# mas-cdc.net
KiCad netlist of a schematic drawn in Altium Designer
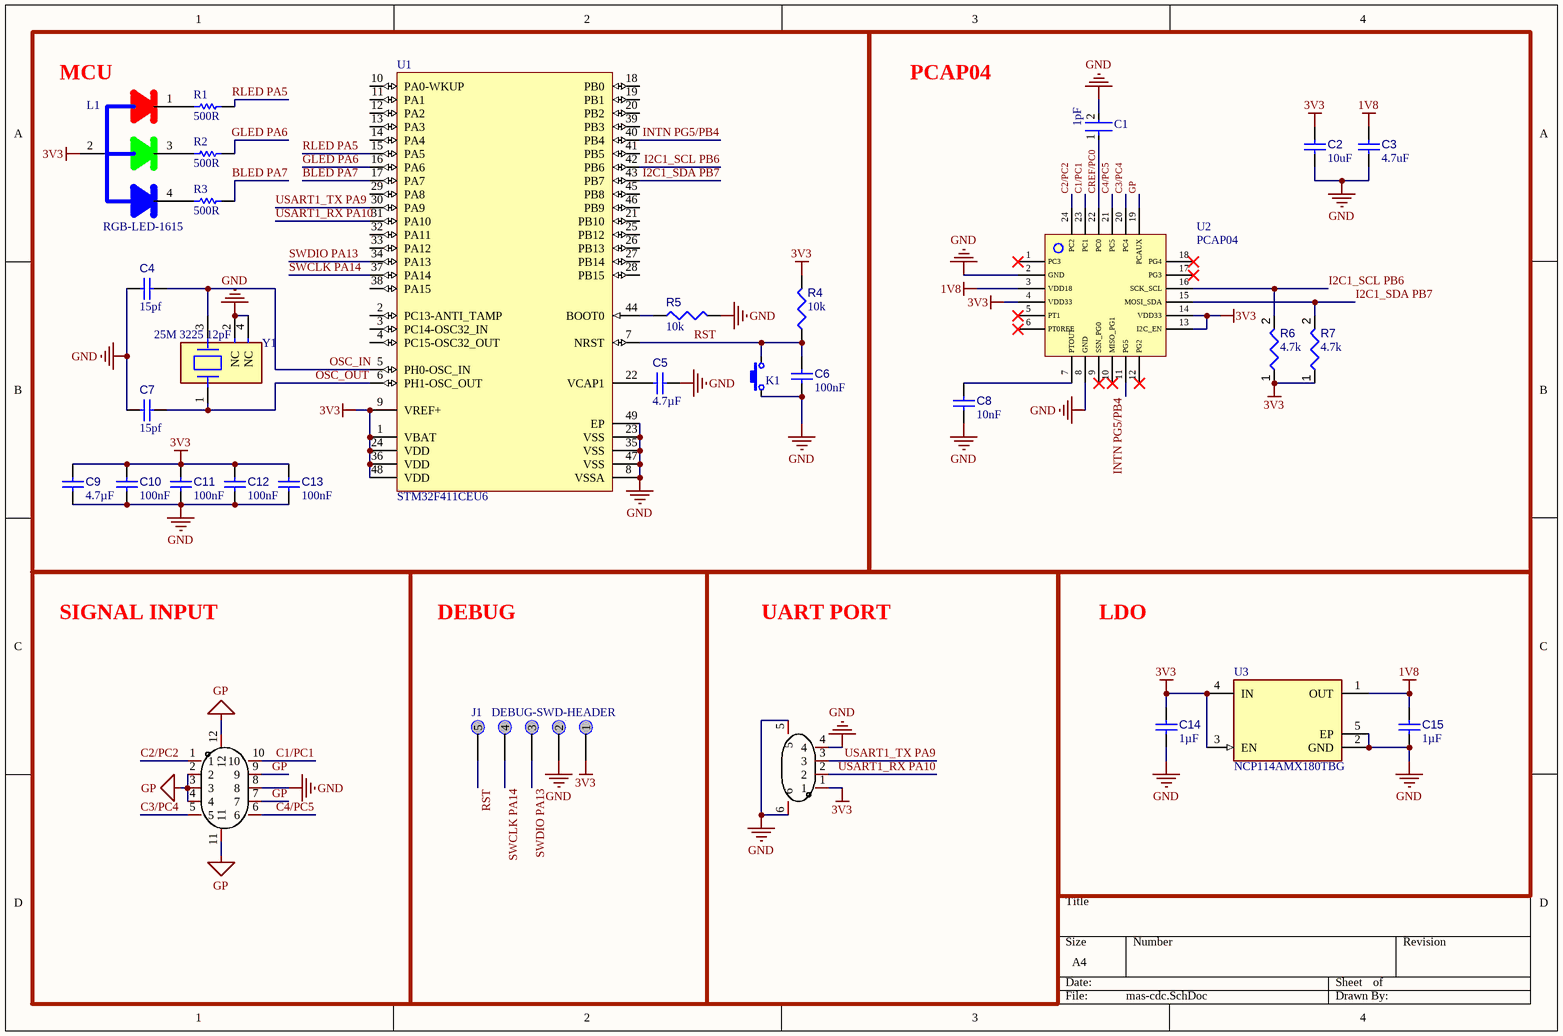
[diagram p0: mas-cdc.SchDoc]

(export (version "E")
  (design (tool "Eeschema 10.0.6"))
  (components
    (comp (ref "C1")
      (value "1pF")
      (footprint "FP-GRM033-0_03-IPC_B")
      (description "Chip Multilayer Ceramic Capacitors for General Purpose, 0201, 1.0pF, C0G, 30ppm/°C, 0.05pF, 50V")
      (libsource (lib "Altium Content Vault") (part "b4654b650e69147ec39a6b967a45e02"))
    )
    (comp (ref "C2")
      (value "10uF")
      (footprint "CAPC0402(1005)60_L")
      (description "Chip Capacitor, 10µF +/-40%, 6.3V, 0402, Thickness 0.6 mm")
      (fields (field (name "TOLERANCE") "10%") (field (name "Comment") "Capacitor 10µF +/-40% 6.3V 0402"))
      (libsource (lib "DigiPCBA Workspace") (part "CAP-NP-2"))
    )
    (comp (ref "C3")
      (value "4.7uF")
      (footprint "CAPC0402(1005)60_L")
      (description "Chip Capacitor, 10µF +/-40%, 6.3V, 0402, Thickness 0.6 mm")
      (fields (field (name "TOLERANCE") "10%") (field (name "Comment") "Capacitor 10µF +/-40% 6.3V 0402"))
      (libsource (lib "DigiPCBA Workspace") (part "CAP-NP-2"))
    )
    (comp (ref "C4")
      (value "15pf")
      (footprint "CAPC0402(1005)60_L")
      (description "Chip Capacitor, 100nF +/-20%, 25V, 0402, Thickness 0.6 mm")
      (fields (field (name "TOLERANCE") "10%") (field (name "Comment") "Capacitor 100nF +/-20% 25V 0402"))
      (libsource (lib "DigiPCBA Workspace") (part "CAP-NP-2"))
    )
    (comp (ref "C5")
      (value "4.7µF")
      (footprint "CAPC0603(1608)100_L")
      (description "Chip Capacitor, 4.7µF +/-20%, 10V, 0603, Thickness 1 mm")
      (fields (field (name "TOLERANCE") "10%") (field (name "Comment") "Capacitor 4.7µF +/-20% 10V 0603"))
      (libsource (lib "DigiPCBA Workspace") (part "CAP-NP-2"))
    )
    (comp (ref "C6")
      (value "100nF")
      (footprint "CAPC0402(1005)60_L")
      (description "Chip Capacitor, 100nF +/-20%, 25V, 0402, Thickness 0.6 mm")
      (fields (field (name "TOLERANCE") "10%") (field (name "Comment") "Capacitor 100nF +/-20% 25V 0402"))
      (libsource (lib "DigiPCBA Workspace") (part "CAP-NP-2"))
    )
    (comp (ref "C7")
      (value "15pf")
      (footprint "CAPC0402(1005)60_L")
      (description "Chip Capacitor, 100nF +/-20%, 25V, 0402, Thickness 0.6 mm")
      (fields (field (name "TOLERANCE") "10%") (field (name "Comment") "Capacitor 100nF +/-20% 25V 0402"))
      (libsource (lib "DigiPCBA Workspace") (part "CAP-NP-2"))
    )
    (comp (ref "C8")
      (value "10nF")
      (footprint "CAPC0402(1005)60_L")
      (description "Chip Capacitor, 10nF +/-20%, 50V, 0402, Thickness 0.6 mm")
      (fields (field (name "TOLERANCE") "5%") (field (name "Comment") "Capacitor 10nF +/-20% 50V 0402"))
      (libsource (lib "DigiPCBA Workspace") (part "CAP-NP-2"))
    )
    (comp (ref "C9")
      (value "4.7µF")
      (footprint "CAPC0603(1608)100_L")
      (description "Chip Capacitor, 4.7µF +/-20%, 10V, 0603, Thickness 1 mm")
      (fields (field (name "TOLERANCE") "10%") (field (name "Comment") "Capacitor 4.7µF +/-20% 10V 0603"))
      (libsource (lib "DigiPCBA Workspace") (part "CAP-NP-2"))
    )
    (comp (ref "C10")
      (value "100nF")
      (footprint "CAPC0402(1005)60_L")
      (description "Chip Capacitor, 100nF +/-20%, 25V, 0402, Thickness 0.6 mm")
      (fields (field (name "TOLERANCE") "10%") (field (name "Comment") "Capacitor 100nF +/-20% 25V 0402"))
      (libsource (lib "DigiPCBA Workspace") (part "CAP-NP-2"))
    )
    (comp (ref "C11")
      (value "100nF")
      (footprint "CAPC0402(1005)60_L")
      (description "Chip Capacitor, 100nF +/-20%, 25V, 0402, Thickness 0.6 mm")
      (fields (field (name "TOLERANCE") "10%") (field (name "Comment") "Capacitor 100nF +/-20% 25V 0402"))
      (libsource (lib "DigiPCBA Workspace") (part "CAP-NP-2"))
    )
    (comp (ref "C12")
      (value "100nF")
      (footprint "CAPC0402(1005)60_L")
      (description "Chip Capacitor, 100nF +/-20%, 25V, 0402, Thickness 0.6 mm")
      (fields (field (name "TOLERANCE") "10%") (field (name "Comment") "Capacitor 100nF +/-20% 25V 0402"))
      (libsource (lib "DigiPCBA Workspace") (part "CAP-NP-2"))
    )
    (comp (ref "C13")
      (value "100nF")
      (footprint "CAPC0402(1005)60_L")
      (description "Chip Capacitor, 100nF +/-20%, 25V, 0402, Thickness 0.6 mm")
      (fields (field (name "TOLERANCE") "10%") (field (name "Comment") "Capacitor 100nF +/-20% 25V 0402"))
      (libsource (lib "DigiPCBA Workspace") (part "CAP-NP-2"))
    )
    (comp (ref "C14")
      (value "1µF")
      (footprint "CAPC0402(1005)60_L")
      (description "Chip Capacitor, 1µF +/-20%, 10V, 0402, Thickness 0.6 mm")
      (fields (field (name "TOLERANCE") "10%") (field (name "Comment") "Capacitor 1µF +/-20% 10V 0402"))
      (libsource (lib "DigiPCBA Workspace") (part "CAP-NP-2"))
    )
    (comp (ref "C15")
      (value "1µF")
      (footprint "CAPC0402(1005)60_L")
      (description "Chip Capacitor, 1µF +/-20%, 10V, 0402, Thickness 0.6 mm")
      (fields (field (name "TOLERANCE") "10%") (field (name "Comment") "Capacitor 1µF +/-20% 10V 0402"))
      (libsource (lib "DigiPCBA Workspace") (part "CAP-NP-2"))
    )
    (comp (ref "CN1")
      (value "SH1.0-4P")
      (footprint "CONN-SMD_4P-P1.00_WF10004-01200")
      (description "连接器")
      (fields (field (name "MANUFACTURER") "ATOM(爱特姆)") (field (name "MANUFACTURER PART") "WF10004-01200"))
      (libsource (lib "LGSchlib") (part "SH1.0-4P"))
    )
    (comp (ref "J1")
      (value "DEBUG-SWD-HEADER")
      (footprint "DEBUG-SWD-HEADER-Footprint-1")
      (description "1.27MM 5P 测试/调试/下载焊点")
      (libsource (lib "DigiPCBA Workspace") (part "DEBUG-SWD-HEADER-Symbol-1"))
    )
    (comp (ref "J2")
      (value "BM24-10DS/2-0.35V(51)")
      (footprint "CONN-SMD_BM24-10DS-2-0.35V-51")
      (description "板对板连接器")
      (fields (field (name "MANUFACTURER") "HRS(广濑)"))
      (libsource (lib "LG_Integrated_Library") (part "BM24-10DS/2-0.35V(51)"))
    )
    (comp (ref "K1")
      (value "Button")
      (footprint "SW-SMD_ST-1185X")
      (libsource (lib "LG_Integrated_Library") (part "Button"))
    )
    (comp (ref "L1")
      (value "RGB-LED-1615")
      (footprint "RGB-LED-1615-Footprint-1")
      (description "RGB LED")
      (libsource (lib "DigiPCBA Workspace") (part "RGB-LED-1615-Symbol-1"))
    )
    (comp (ref "R1")
      (value "500R")
      (footprint "RESC0603X26X15ML03T05")
      (fields (field (name "PART NUMBER") "RK73H1HTTC1002F") (field (name "MANUFACTURER") "KOA Speer"))
      (libsource (lib "Altium Content Vault") (part "RES"))
    )
    (comp (ref "R2")
      (value "500R")
      (footprint "RESC0603X26X15ML03T05")
      (fields (field (name "PART NUMBER") "RK73H1HTTC1002F") (field (name "MANUFACTURER") "KOA Speer"))
      (libsource (lib "Altium Content Vault") (part "RES"))
    )
    (comp (ref "R3")
      (value "500R")
      (footprint "RESC0603X26X15ML03T05")
      (fields (field (name "PART NUMBER") "RK73H1HTTC1002F") (field (name "MANUFACTURER") "KOA Speer"))
      (libsource (lib "Altium Content Vault") (part "RES"))
    )
    (comp (ref "R4")
      (value "10k")
      (footprint "RESC0402(1005)_L")
      (description "Chip Resistor, 10 kOhms, +/-1 %, 63 mW, -55 to 125 degC, 0402")
      (fields (field (name "POWER") "63mW") (field (name "TOLERANCE") "1%"))
      (libsource (lib "") (part "RES-2_1"))
    )
    (comp (ref "R5")
      (value "10k")
      (footprint "RESC0402(1005)_L")
      (description "Chip Resistor, 10 kOhms, +/-1 %, 63 mW, -55 to 125 degC, 0402")
      (fields (field (name "POWER") "63mW") (field (name "TOLERANCE") "1%"))
      (libsource (lib "") (part "RES-2_1"))
    )
    (comp (ref "R6")
      (value "4.7k")
      (footprint "RESC0402(1005)_L")
      (description "Chip Resistor, 4,7 kOhms, +/-1 %, 63 mW, -55 to 155 degC, 0402")
      (fields (field (name "POWER") "63mW") (field (name "TOLERANCE") "1%"))
      (libsource (lib "DigiPCBA Workspace") (part "RES-2"))
    )
    (comp (ref "R7")
      (value "4.7k")
      (footprint "RESC0402(1005)_L")
      (description "Chip Resistor, 4,7 kOhms, +/-1 %, 63 mW, -55 to 155 degC, 0402")
      (fields (field (name "POWER") "63mW") (field (name "TOLERANCE") "1%"))
      (libsource (lib "DigiPCBA Workspace") (part "RES-2"))
    )
    (comp (ref "U1")
      (value "STM32F411CEU6")
      (footprint "STM-UFQFPN48_L")
      (libsource (lib "LG_Integrated_Library") (part "STM32F411CEU6-2"))
    )
    (comp (ref "U2")
      (value "PCAP04")
      (footprint "QFN-24-PAD")
      (description "CDC IC")
      (libsource (lib "LG_Integrated_Library") (part "PCAP04"))
    )
    (comp (ref "U3")
      (value "NCP114AMX180TBG")
      (footprint "FP-517CU-MFG")
      (description "IC REG LINEAR 1.8V 300MA 4UDFN")
      (fields
        (field (name "MANUFACTURER") "ON Semiconductor")
        (field (name "OCTOPART") "https://octopart.com/ncp114amx180tbg-on+semiconductor-56808172")
      )
      (libsource (lib "Altium Content Vault") (part "d482fde4c46c8d3b68fd86b21119a5c"))
    )
    (comp (ref "Y1")
      (value "25M 3225 12pF")
      (footprint "FP-CX3225GB-MFG")
      (description "CRYSTAL 16.0000MHZ 8PF SMD")
      (fields (field (name "TOLERANCE") "20ppm"))
      (libsource (lib "Altium Content Vault") (part "485821f88a3d0e4767168cc8d80ed41"))
    )
  )
  (nets
    (net (code "1") (name "/BLED PA7") (class "Default")
      (node (ref "R3") (pin "2") (pinfunction "2_2") (pintype "passive"))
      (node (ref "U1") (pin "17") (pinfunction "PA7_17") (pintype "bidirectional"))
    )
    (net (code "2") (name "/C1{slash}PC1") (class "Default")
      (node (ref "J2") (pin "10") (pinfunction "10_10") (pintype "passive"))
      (node (ref "U2") (pin "23") (pinfunction "PC1_23") (pintype "passive"))
    )
    (net (code "3") (name "/C2{slash}PC2") (class "Default")
      (node (ref "J2") (pin "1") (pinfunction "1_1") (pintype "passive"))
      (node (ref "U2") (pin "24") (pinfunction "PC2_24") (pintype "passive"))
    )
    (net (code "4") (name "/C3{slash}PC4") (class "Default")
      (node (ref "J2") (pin "5") (pinfunction "5_5") (pintype "passive"))
      (node (ref "U2") (pin "20") (pinfunction "PC4_20") (pintype "passive"))
    )
    (net (code "5") (name "/C4{slash}PC5") (class "Default")
      (node (ref "J2") (pin "6") (pinfunction "6_6") (pintype "passive"))
      (node (ref "U2") (pin "21") (pinfunction "PC5_21") (pintype "passive"))
    )
    (net (code "6") (name "/CREF{slash}PC0") (class "Default")
      (node (ref "C1") (pin "1") (pinfunction "1_1") (pintype "passive"))
      (node (ref "U2") (pin "22") (pinfunction "PC0_22") (pintype "passive"))
    )
    (net (code "7") (name "/GLED PA6") (class "Default")
      (node (ref "R2") (pin "2") (pinfunction "2_2") (pintype "passive"))
      (node (ref "U1") (pin "16") (pinfunction "PA6_16") (pintype "bidirectional"))
    )
    (net (code "8") (name "/I2C1_SCL PB6") (class "Default")
      (node (ref "R6") (pin "2") (pinfunction "2_2") (pintype "passive"))
      (node (ref "U1") (pin "42") (pinfunction "PB6_42") (pintype "bidirectional"))
      (node (ref "U2") (pin "16") (pinfunction "SCK_SCL_16") (pintype "passive"))
    )
    (net (code "9") (name "/I2C1_SDA PB7") (class "Default")
      (node (ref "R7") (pin "2") (pinfunction "2_2") (pintype "passive"))
      (node (ref "U1") (pin "43") (pinfunction "PB7_43") (pintype "bidirectional"))
      (node (ref "U2") (pin "15") (pinfunction "MOSI_SDA_15") (pintype "passive"))
    )
    (net (code "10") (name "/INTN PG5{slash}PB4") (class "Default")
      (node (ref "U1") (pin "40") (pinfunction "PB4_40") (pintype "bidirectional"))
      (node (ref "U2") (pin "11") (pinfunction "PG5_11") (pintype "passive"))
    )
    (net (code "11") (name "/OSC_IN") (class "Default")
      (node (ref "C4") (pin "1") (pinfunction "1_1") (pintype "passive"))
      (node (ref "U1") (pin "5") (pinfunction "PH0-OSC_IN_5") (pintype "bidirectional"))
      (node (ref "Y1") (pin "3") (pinfunction "2_HOT_3") (pintype "passive"))
    )
    (net (code "12") (name "/OSC_OUT") (class "Default")
      (node (ref "C7") (pin "1") (pinfunction "1_1") (pintype "passive"))
      (node (ref "U1") (pin "6") (pinfunction "PH1-OSC_OUT_6") (pintype "bidirectional"))
      (node (ref "Y1") (pin "1") (pinfunction "1_HOT_1") (pintype "passive"))
    )
    (net (code "13") (name "/RLED PA5") (class "Default")
      (node (ref "R1") (pin "2") (pinfunction "2_2") (pintype "passive"))
      (node (ref "U1") (pin "15") (pinfunction "PA5_15") (pintype "bidirectional"))
    )
    (net (code "14") (name "/RST") (class "Default")
      (node (ref "C6") (pin "2") (pinfunction "2_2") (pintype "passive"))
      (node (ref "J1") (pin "5") (pinfunction "5_5") (pintype "passive"))
      (node (ref "K1") (pin "2") (pinfunction "2_2") (pintype "passive"))
      (node (ref "R4") (pin "1") (pinfunction "1_1") (pintype "passive"))
      (node (ref "U1") (pin "7") (pinfunction "NRST_7") (pintype "bidirectional"))
    )
    (net (code "15") (name "/SWCLK PA14") (class "Default")
      (node (ref "J1") (pin "4") (pinfunction "4_4") (pintype "passive"))
      (node (ref "U1") (pin "37") (pinfunction "PA14_37") (pintype "bidirectional"))
    )
    (net (code "16") (name "/SWDIO PA13") (class "Default")
      (node (ref "J1") (pin "3") (pinfunction "3_3") (pintype "passive"))
      (node (ref "U1") (pin "34") (pinfunction "PA13_34") (pintype "bidirectional"))
    )
    (net (code "17") (name "/USART1_RX PA10") (class "Default")
      (node (ref "CN1") (pin "2") (pinfunction "2_2") (pintype "passive"))
      (node (ref "U1") (pin "31") (pinfunction "PA10_31") (pintype "bidirectional"))
    )
    (net (code "18") (name "/USART1_TX PA9") (class "Default")
      (node (ref "CN1") (pin "3") (pinfunction "3_3") (pintype "passive"))
      (node (ref "U1") (pin "30") (pinfunction "PA9_30") (pintype "bidirectional"))
    )
    (net (code "19") (name "1V8") (class "Default")
      (node (ref "C15") (pin "1") (pinfunction "1_1") (pintype "passive"))
      (node (ref "C3") (pin "2") (pinfunction "2_2") (pintype "passive"))
      (node (ref "U2") (pin "3") (pinfunction "VDD18_3") (pintype "passive"))
      (node (ref "U3") (pin "1") (pinfunction "OUT_1") (pintype "power_in"))
    )
    (net (code "20") (name "3V3") (class "Default")
      (node (ref "C10") (pin "2") (pinfunction "2_2") (pintype "passive"))
      (node (ref "C11") (pin "2") (pinfunction "2_2") (pintype "passive"))
      (node (ref "C12") (pin "2") (pinfunction "2_2") (pintype "passive"))
      (node (ref "C13") (pin "2") (pinfunction "2_2") (pintype "passive"))
      (node (ref "C14") (pin "1") (pinfunction "1_1") (pintype "passive"))
      (node (ref "C2") (pin "2") (pinfunction "2_2") (pintype "passive"))
      (node (ref "C9") (pin "2") (pinfunction "2_2") (pintype "passive"))
      (node (ref "CN1") (pin "1") (pinfunction "1_1") (pintype "passive"))
      (node (ref "J1") (pin "1") (pinfunction "1_1") (pintype "passive"))
      (node (ref "L1") (pin "2") (pinfunction "COM+_2") (pintype "passive"))
      (node (ref "R4") (pin "2") (pinfunction "2_2") (pintype "passive"))
      (node (ref "R6") (pin "1") (pinfunction "1_1") (pintype "passive"))
      (node (ref "R7") (pin "1") (pinfunction "1_1") (pintype "passive"))
      (node (ref "U1") (pin "1") (pinfunction "VBAT_1") (pintype "power_in"))
      (node (ref "U1") (pin "24") (pinfunction "VDD_24") (pintype "power_in"))
      (node (ref "U1") (pin "36") (pinfunction "VDD_36") (pintype "power_in"))
      (node (ref "U1") (pin "48") (pinfunction "VDD_48") (pintype "power_in"))
      (node (ref "U1") (pin "9") (pinfunction "VREF+_9") (pintype "power_in"))
      (node (ref "U2") (pin "13") (pinfunction "I2C_EN_13") (pintype "passive"))
      (node (ref "U2") (pin "14") (pinfunction "VDD33_14") (pintype "passive"))
      (node (ref "U2") (pin "4") (pinfunction "VDD33_4") (pintype "passive"))
      (node (ref "U3") (pin "3") (pinfunction "EN_3") (pintype "input"))
      (node (ref "U3") (pin "4") (pinfunction "IN_4") (pintype "power_in"))
    )
    (net (code "21") (name "GND") (class "Default")
      (node (ref "C1") (pin "2") (pinfunction "2_2") (pintype "passive"))
      (node (ref "C10") (pin "1") (pinfunction "1_1") (pintype "passive"))
      (node (ref "C11") (pin "1") (pinfunction "1_1") (pintype "passive"))
      (node (ref "C12") (pin "1") (pinfunction "1_1") (pintype "passive"))
      (node (ref "C13") (pin "1") (pinfunction "1_1") (pintype "passive"))
      (node (ref "C14") (pin "2") (pinfunction "2_2") (pintype "passive"))
      (node (ref "C15") (pin "2") (pinfunction "2_2") (pintype "passive"))
      (node (ref "C2") (pin "1") (pinfunction "1_1") (pintype "passive"))
      (node (ref "C3") (pin "1") (pinfunction "1_1") (pintype "passive"))
      (node (ref "C4") (pin "2") (pinfunction "2_2") (pintype "passive"))
      (node (ref "C5") (pin "2") (pinfunction "2_2") (pintype "passive"))
      (node (ref "C6") (pin "1") (pinfunction "1_1") (pintype "passive"))
      (node (ref "C7") (pin "2") (pinfunction "2_2") (pintype "passive"))
      (node (ref "C8") (pin "1") (pinfunction "1_1") (pintype "passive"))
      (node (ref "C9") (pin "1") (pinfunction "1_1") (pintype "passive"))
      (node (ref "CN1") (pin "4") (pinfunction "4_4") (pintype "passive"))
      (node (ref "CN1") (pin "5") (pinfunction "5_5") (pintype "passive"))
      (node (ref "CN1") (pin "6") (pinfunction "6_6") (pintype "passive"))
      (node (ref "J1") (pin "2") (pinfunction "2_2") (pintype "passive"))
      (node (ref "J2") (pin "8") (pinfunction "8_8") (pintype "passive"))
      (node (ref "K1") (pin "1") (pinfunction "1_1") (pintype "passive"))
      (node (ref "R5") (pin "2") (pinfunction "2_2") (pintype "passive"))
      (node (ref "U1") (pin "23") (pinfunction "VSS_23") (pintype "power_in"))
      (node (ref "U1") (pin "35") (pinfunction "VSS_35") (pintype "power_in"))
      (node (ref "U1") (pin "47") (pinfunction "VSS_47") (pintype "power_in"))
      (node (ref "U1") (pin "49") (pinfunction "EP_49") (pintype "power_in"))
      (node (ref "U1") (pin "8") (pinfunction "VSSA_8") (pintype "power_in"))
      (node (ref "U2") (pin "2") (pinfunction "GND_2") (pintype "passive"))
      (node (ref "U2") (pin "8") (pinfunction "GND_8") (pintype "passive"))
      (node (ref "U3") (pin "2") (pinfunction "GND_2") (pintype "power_in"))
      (node (ref "U3") (pin "5") (pinfunction "EP_5") (pintype "power_in"))
      (node (ref "Y1") (pin "2") (pinfunction "NC_2") (pintype "passive"))
      (node (ref "Y1") (pin "4") (pinfunction "NC_4") (pintype "passive"))
    )
    (net (code "22") (name "GP") (class "Default")
      (node (ref "J2") (pin "11") (pinfunction "11_11") (pintype "passive"))
      (node (ref "J2") (pin "12") (pinfunction "12_12") (pintype "passive"))
      (node (ref "J2") (pin "2") (pinfunction "2_2") (pintype "passive"))
      (node (ref "J2") (pin "3") (pinfunction "3_3") (pintype "passive"))
      (node (ref "J2") (pin "4") (pinfunction "4_4") (pintype "passive"))
      (node (ref "J2") (pin "7") (pinfunction "7_7") (pintype "passive"))
      (node (ref "J2") (pin "9") (pinfunction "9_9") (pintype "passive"))
      (node (ref "U2") (pin "19") (pinfunction "PCAUX_19") (pintype "passive"))
    )
    (net (code "23") (name "Net-(L1-B)") (class "Default")
      (node (ref "L1") (pin "4") (pinfunction "B_4") (pintype "passive"))
      (node (ref "R3") (pin "1") (pinfunction "1_1") (pintype "passive"))
    )
    (net (code "24") (name "Net-(L1-G)") (class "Default")
      (node (ref "L1") (pin "3") (pinfunction "G_3") (pintype "passive"))
      (node (ref "R2") (pin "1") (pinfunction "1_1") (pintype "passive"))
    )
    (net (code "25") (name "Net-(L1-R)") (class "Default")
      (node (ref "L1") (pin "1") (pinfunction "R_1") (pintype "passive"))
      (node (ref "R1") (pin "1") (pinfunction "1_1") (pintype "passive"))
    )
    (net (code "26") (name "Net-(U1-BOOT0)") (class "Default")
      (node (ref "R5") (pin "1") (pinfunction "1_1") (pintype "passive"))
      (node (ref "U1") (pin "44") (pinfunction "BOOT0_44") (pintype "input"))
    )
    (net (code "27") (name "Net-(U1-VCAP1)") (class "Default")
      (node (ref "C5") (pin "1") (pinfunction "1_1") (pintype "passive"))
      (node (ref "U1") (pin "22") (pinfunction "VCAP1_22") (pintype "passive"))
    )
    (net (code "28") (name "Net-(U2-PTOUT)") (class "Default")
      (node (ref "C8") (pin "2") (pinfunction "2_2") (pintype "passive"))
      (node (ref "U2") (pin "7") (pinfunction "PTOUT_7") (pintype "passive"))
    )
    (net (code "29") (name "unconnected-(U1-PA0-WKUP-Pad10)") (class "Default")
      (node (ref "U1") (pin "10") (pinfunction "PA0-WKUP_10") (pintype "bidirectional"))
    )
    (net (code "30") (name "unconnected-(U1-PA1-Pad11)") (class "Default")
      (node (ref "U1") (pin "11") (pinfunction "PA1_11") (pintype "bidirectional"))
    )
    (net (code "31") (name "unconnected-(U1-PA2-Pad12)") (class "Default")
      (node (ref "U1") (pin "12") (pinfunction "PA2_12") (pintype "bidirectional"))
    )
    (net (code "32") (name "unconnected-(U1-PA3-Pad13)") (class "Default")
      (node (ref "U1") (pin "13") (pinfunction "PA3_13") (pintype "bidirectional"))
    )
    (net (code "33") (name "unconnected-(U1-PA4-Pad14)") (class "Default")
      (node (ref "U1") (pin "14") (pinfunction "PA4_14") (pintype "bidirectional"))
    )
    (net (code "34") (name "unconnected-(U1-PA8-Pad29)") (class "Default")
      (node (ref "U1") (pin "29") (pinfunction "PA8_29") (pintype "bidirectional"))
    )
    (net (code "35") (name "unconnected-(U1-PA11-Pad32)") (class "Default")
      (node (ref "U1") (pin "32") (pinfunction "PA11_32") (pintype "bidirectional"))
    )
    (net (code "36") (name "unconnected-(U1-PA12-Pad33)") (class "Default")
      (node (ref "U1") (pin "33") (pinfunction "PA12_33") (pintype "bidirectional"))
    )
    (net (code "37") (name "unconnected-(U1-PA15-Pad38)") (class "Default")
      (node (ref "U1") (pin "38") (pinfunction "PA15_38") (pintype "bidirectional"))
    )
    (net (code "38") (name "unconnected-(U1-PB0-Pad18)") (class "Default")
      (node (ref "U1") (pin "18") (pinfunction "PB0_18") (pintype "bidirectional"))
    )
    (net (code "39") (name "unconnected-(U1-PB1-Pad19)") (class "Default")
      (node (ref "U1") (pin "19") (pinfunction "PB1_19") (pintype "bidirectional"))
    )
    (net (code "40") (name "unconnected-(U1-PB2-Pad20)") (class "Default")
      (node (ref "U1") (pin "20") (pinfunction "PB2_20") (pintype "bidirectional"))
    )
    (net (code "41") (name "unconnected-(U1-PB3-Pad39)") (class "Default")
      (node (ref "U1") (pin "39") (pinfunction "PB3_39") (pintype "bidirectional"))
    )
    (net (code "42") (name "unconnected-(U1-PB5-Pad41)") (class "Default")
      (node (ref "U1") (pin "41") (pinfunction "PB5_41") (pintype "bidirectional"))
    )
    (net (code "43") (name "unconnected-(U1-PB8-Pad45)") (class "Default")
      (node (ref "U1") (pin "45") (pinfunction "PB8_45") (pintype "bidirectional"))
    )
    (net (code "44") (name "unconnected-(U1-PB9-Pad46)") (class "Default")
      (node (ref "U1") (pin "46") (pinfunction "PB9_46") (pintype "bidirectional"))
    )
    (net (code "45") (name "unconnected-(U1-PB10-Pad21)") (class "Default")
      (node (ref "U1") (pin "21") (pinfunction "PB10_21") (pintype "bidirectional"))
    )
    (net (code "46") (name "unconnected-(U1-PB12-Pad25)") (class "Default")
      (node (ref "U1") (pin "25") (pinfunction "PB12_25") (pintype "bidirectional"))
    )
    (net (code "47") (name "unconnected-(U1-PB13-Pad26)") (class "Default")
      (node (ref "U1") (pin "26") (pinfunction "PB13_26") (pintype "bidirectional"))
    )
    (net (code "48") (name "unconnected-(U1-PB14-Pad27)") (class "Default")
      (node (ref "U1") (pin "27") (pinfunction "PB14_27") (pintype "bidirectional"))
    )
    (net (code "49") (name "unconnected-(U1-PB15-Pad28)") (class "Default")
      (node (ref "U1") (pin "28") (pinfunction "PB15_28") (pintype "bidirectional"))
    )
    (net (code "50") (name "unconnected-(U1-PC13-ANTI_TAMP-Pad2)") (class "Default")
      (node (ref "U1") (pin "2") (pinfunction "PC13-ANTI_TAMP_2") (pintype "bidirectional"))
    )
    (net (code "51") (name "unconnected-(U1-PC14-OSC32_IN-Pad3)") (class "Default")
      (node (ref "U1") (pin "3") (pinfunction "PC14-OSC32_IN_3") (pintype "bidirectional"))
    )
    (net (code "52") (name "unconnected-(U1-PC15-OSC32_OUT-Pad4)") (class "Default")
      (node (ref "U1") (pin "4") (pinfunction "PC15-OSC32_OUT_4") (pintype "bidirectional"))
    )
    (net (code "53") (name "unconnected-(U2-MISO_PG1-Pad10)") (class "Default")
      (node (ref "U2") (pin "10") (pinfunction "MISO_PG1_10") (pintype "passive+no_connect"))
    )
    (net (code "54") (name "unconnected-(U2-PC3-Pad1)") (class "Default")
      (node (ref "U2") (pin "1") (pinfunction "PC3_1") (pintype "passive+no_connect"))
    )
    (net (code "55") (name "unconnected-(U2-PG2-Pad12)") (class "Default")
      (node (ref "U2") (pin "12") (pinfunction "PG2_12") (pintype "passive+no_connect"))
    )
    (net (code "56") (name "unconnected-(U2-PG3-Pad17)") (class "Default")
      (node (ref "U2") (pin "17") (pinfunction "PG3_17") (pintype "passive+no_connect"))
    )
    (net (code "57") (name "unconnected-(U2-PG4-Pad18)") (class "Default")
      (node (ref "U2") (pin "18") (pinfunction "PG4_18") (pintype "passive+no_connect"))
    )
    (net (code "58") (name "unconnected-(U2-PT0REF-Pad6)") (class "Default")
      (node (ref "U2") (pin "6") (pinfunction "PT0REF_6") (pintype "passive+no_connect"))
    )
    (net (code "59") (name "unconnected-(U2-PT1-Pad5)") (class "Default")
      (node (ref "U2") (pin "5") (pinfunction "PT1_5") (pintype "passive+no_connect"))
    )
    (net (code "60") (name "unconnected-(U2-SSN_PG0-Pad9)") (class "Default")
      (node (ref "U2") (pin "9") (pinfunction "SSN_PG0_9") (pintype "passive+no_connect"))
    )
  )
)
